# 01_MAIN.net
KiCad netlist of a schematic drawn in Altium Designer
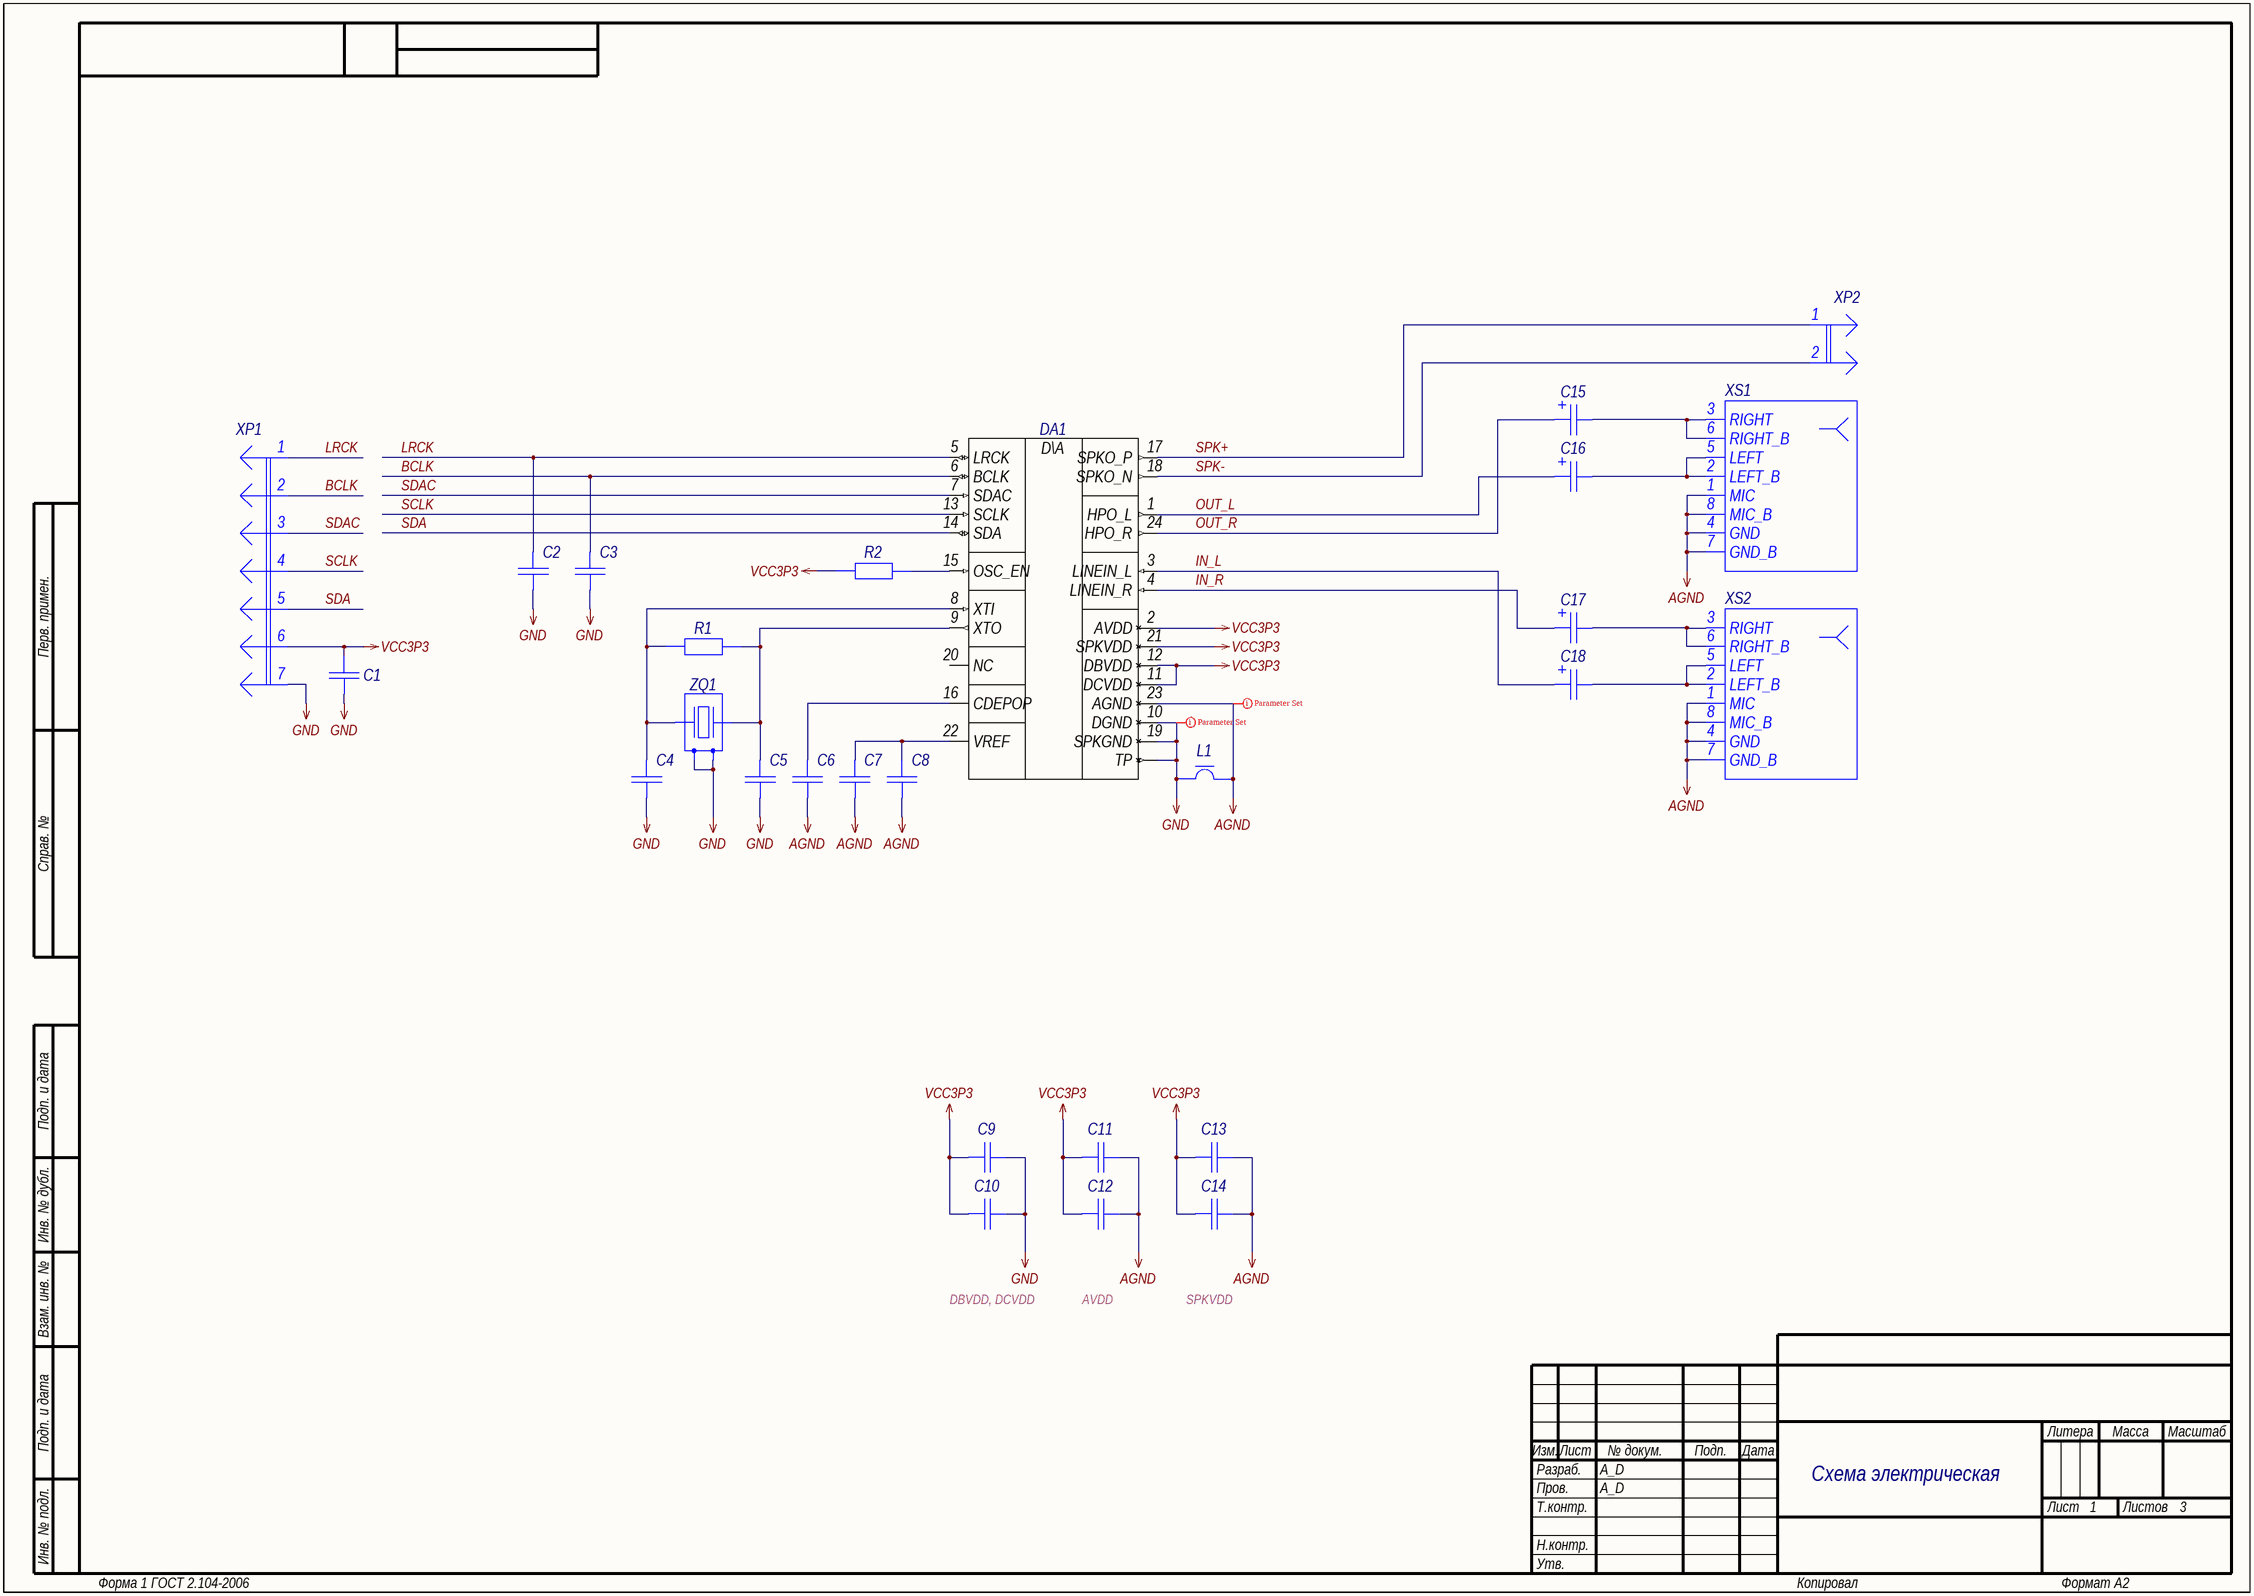
[diagram p0: 01_MAIN.SchDoc]

(export (version "E")
  (design (tool "Eeschema 10.0.6"))
  (components
    (comp (ref "C1")
      (value "Capacitor")
      (footprint "C0805_L")
      (fields
        (field (name "PART NUMBER") "GRM21BR60J226ME39L")
        (field (name "VOLTAGE") "6.3V")
        (field (name "TOLERANCE") "±20%")
        (field (name "PUBLISHER") "Andrew Danich")
      )
      (libsource (lib "ADLib") (part "Capacitor"))
    )
    (comp (ref "C2")
      (value "Capacitor")
      (footprint "C0603_L")
      (fields
        (field (name "PART NUMBER") "GRM1885C1H220JA01D")
        (field (name "VOLTAGE") "50V")
        (field (name "TOLERANCE") "±5%")
        (field (name "PUBLISHER") "Andrew Danich")
      )
      (libsource (lib "ADLib") (part "Capacitor"))
    )
    (comp (ref "C3")
      (value "Capacitor")
      (footprint "C0603_L")
      (fields
        (field (name "PART NUMBER") "GRM1885C1H220JA01D")
        (field (name "VOLTAGE") "50V")
        (field (name "TOLERANCE") "±5%")
        (field (name "PUBLISHER") "Andrew Danich")
      )
      (libsource (lib "ADLib") (part "Capacitor"))
    )
    (comp (ref "C4")
      (value "Capacitor")
      (footprint "C0603_L")
      (fields
        (field (name "PART NUMBER") "GCM1885C2A120JA16D")
        (field (name "VOLTAGE") "100V")
        (field (name "TOLERANCE") "±5%")
        (field (name "PUBLISHER") "Andrew Danich")
      )
      (libsource (lib "ADLib") (part "Capacitor"))
    )
    (comp (ref "C5")
      (value "Capacitor")
      (footprint "C0603_L")
      (fields
        (field (name "PART NUMBER") "GCM1885C2A120JA16D")
        (field (name "VOLTAGE") "100V")
        (field (name "TOLERANCE") "±5%")
        (field (name "PUBLISHER") "Andrew Danich")
      )
      (libsource (lib "ADLib") (part "Capacitor"))
    )
    (comp (ref "C6")
      (value "Capacitor")
      (footprint "C0603_L")
      (fields
        (field (name "PART NUMBER") "GCM188R71E105KA64D")
        (field (name "VOLTAGE") "25V")
        (field (name "TOLERANCE") "±10%")
        (field (name "PUBLISHER") "Andrew Danich")
      )
      (libsource (lib "ADLib") (part "Capacitor"))
    )
    (comp (ref "C7")
      (value "Capacitor")
      (footprint "C0603_L")
      (fields
        (field (name "PART NUMBER") "GRM188R72A104KA35D")
        (field (name "VOLTAGE") "100V")
        (field (name "TOLERANCE") "±10%")
        (field (name "PUBLISHER") "Andrew Danich")
      )
      (libsource (lib "ADLib") (part "Capacitor"))
    )
    (comp (ref "C8")
      (value "Capacitor")
      (footprint "C0603_L")
      (fields
        (field (name "PART NUMBER") "GRT188C81E475KE13D")
        (field (name "VOLTAGE") "25V")
        (field (name "TOLERANCE") "±20%")
        (field (name "PUBLISHER") "Andrew Danich")
      )
      (libsource (lib "ADLib") (part "Capacitor"))
    )
    (comp (ref "C9")
      (value "Capacitor")
      (footprint "C0603_L")
      (fields
        (field (name "PART NUMBER") "GCM188R71E105KA64D")
        (field (name "VOLTAGE") "25V")
        (field (name "TOLERANCE") "±10%")
        (field (name "PUBLISHER") "Andrew Danich")
      )
      (libsource (lib "ADLib") (part "Capacitor"))
    )
    (comp (ref "C10")
      (value "Capacitor")
      (footprint "C0603_L")
      (fields
        (field (name "PART NUMBER") "GRM1885C2A102JA01D")
        (field (name "VOLTAGE") "100V")
        (field (name "TOLERANCE") "±5%")
        (field (name "PUBLISHER") "Andrew Danich")
      )
      (libsource (lib "ADLib") (part "Capacitor"))
    )
    (comp (ref "C11")
      (value "Capacitor")
      (footprint "C0603_L")
      (fields
        (field (name "PART NUMBER") "GCM188R71E105KA64D")
        (field (name "VOLTAGE") "25V")
        (field (name "TOLERANCE") "±10%")
        (field (name "PUBLISHER") "Andrew Danich")
      )
      (libsource (lib "ADLib") (part "Capacitor"))
    )
    (comp (ref "C12")
      (value "Capacitor")
      (footprint "C0603_L")
      (fields
        (field (name "PART NUMBER") "GRM1885C2A102JA01D")
        (field (name "VOLTAGE") "100V")
        (field (name "TOLERANCE") "±5%")
        (field (name "PUBLISHER") "Andrew Danich")
      )
      (libsource (lib "ADLib") (part "Capacitor"))
    )
    (comp (ref "C13")
      (value "Capacitor")
      (footprint "C0603_L")
      (fields
        (field (name "PART NUMBER") "GRM188C80J106MA73D")
        (field (name "VOLTAGE") "6.3V")
        (field (name "TOLERANCE") "±20%")
        (field (name "PUBLISHER") "Andrew Danich")
      )
      (libsource (lib "ADLib") (part "Capacitor"))
    )
    (comp (ref "C14")
      (value "Capacitor")
      (footprint "C0603_L")
      (fields
        (field (name "PART NUMBER") "GRM1885C2A102JA01D")
        (field (name "VOLTAGE") "100V")
        (field (name "TOLERANCE") "±5%")
        (field (name "PUBLISHER") "Andrew Danich")
      )
      (libsource (lib "ADLib") (part "Capacitor"))
    )
    (comp (ref "C15")
      (value "Capacitor-T")
      (footprint "C3528-p")
      (fields
        (field (name "PART NUMBER") "T520B107M006ATE040")
        (field (name "VOLTAGE") "6.3V")
        (field (name "TOLERANCE") "±20%")
        (field (name "PUBLISHER") "Andrew Danich")
      )
      (libsource (lib "ADLib") (part "Capacitor-T"))
    )
    (comp (ref "C16")
      (value "Capacitor-T")
      (footprint "C3528-p")
      (fields
        (field (name "PART NUMBER") "T520B107M006ATE040")
        (field (name "VOLTAGE") "6.3V")
        (field (name "TOLERANCE") "±20%")
        (field (name "PUBLISHER") "Andrew Danich")
      )
      (libsource (lib "ADLib") (part "Capacitor-T"))
    )
    (comp (ref "C17")
      (value "Capacitor-T")
      (footprint "C3216-p")
      (fields
        (field (name "PART NUMBER") "293D105X9016A2TE3")
        (field (name "VOLTAGE") "16V")
        (field (name "TOLERANCE") "±10%")
        (field (name "PUBLISHER") "Andrew Danich")
      )
      (libsource (lib "ADLib") (part "Capacitor-T"))
    )
    (comp (ref "C18")
      (value "Capacitor-T")
      (footprint "C3216-p")
      (fields
        (field (name "PART NUMBER") "293D105X9016A2TE3")
        (field (name "VOLTAGE") "16V")
        (field (name "TOLERANCE") "±10%")
        (field (name "PUBLISHER") "Andrew Danich")
      )
      (libsource (lib "ADLib") (part "Capacitor-T"))
    )
    (comp (ref "DA1")
      (value "ALC5628")
      (footprint "QFN-24_050P400X400X090_N")
      (fields
        (field (name "PART NUMBER") "ALC5628-GR")
        (field (name "MANUFACTURER") "Realtek")
        (field (name "PUBLISHER") "Andrew Danich")
      )
      (libsource (lib "ADLib") (part "ALC5628"))
    )
    (comp (ref "L1")
      (value "FerriteBead")
      (footprint "L0603_L")
      (fields
        (field (name "PART NUMBER") "BLM18PG121SN1")
        (field (name "MANUFACTURER") "Murata")
        (field (name "PUBLISHER") "Andrew Danich")
      )
      (libsource (lib "ADLib") (part "FerriteBead"))
    )
    (comp (ref "R1")
      (value "Resistor")
      (footprint "R0603_L")
      (fields
        (field (name "PART NUMBER") "RC0603JR-071ML")
        (field (name "TOLERANCE") "±5%")
        (field (name "MANUFACTURER") "Yageo")
        (field (name "PUBLISHER") "Andrew Danich")
      )
      (libsource (lib "ADLib") (part "Resistor"))
    )
    (comp (ref "R2")
      (value "Resistor")
      (footprint "R0603_L")
      (fields
        (field (name "PART NUMBER") "RC0603JR-070R")
        (field (name "TOLERANCE") "±5%")
        (field (name "MANUFACTURER") "Yageo")
        (field (name "PUBLISHER") "Andrew Danich")
      )
      (libsource (lib "ADLib") (part "Resistor"))
    )
    (comp (ref "XP1")
      (value "Text")
      (footprint "PLS-7")
      (fields (field (name "PART NUMBER") "PLS-7") (field (name "PUBLISHER") "Andrew Danich"))
      (libsource (lib "ADLib") (part "Con-7-M"))
    )
    (comp (ref "XP2")
      (value "SPK")
      (footprint "PLS-2")
      (fields (field (name "PART NUMBER") "PLS-2") (field (name "PUBLISHER") "Andrew Danich"))
      (libsource (lib "ADLib") (part "Con-2-M"))
    )
    (comp (ref "XS1")
      (value "OUT")
      (footprint "PJ30930-Series")
      (fields
        (field (name "PART NUMBER") "PJ30930-Q-LC0AG00TR-7260")
        (field (name "MANUFACTURER") "Dongnan Electronics")
        (field (name "PUBLISHER") "Andrew Danich")
      )
      (libsource (lib "ADLib") (part "PJ30930-Q-LCxx00x-7260"))
    )
    (comp (ref "XS2")
      (value "IN")
      (footprint "PJ30930-Series")
      (fields
        (field (name "PART NUMBER") "PJ30930-Q-LC0AG00TR-7260")
        (field (name "MANUFACTURER") "Dongnan Electronics")
        (field (name "PUBLISHER") "Andrew Danich")
      )
      (libsource (lib "ADLib") (part "PJ30930-Q-LCxx00x-7260"))
    )
    (comp (ref "ZQ1")
      (value "Crystal-1_3p_S")
      (footprint "SMD 3.2x2.5mm")
      (fields
        (field (name "PART NUMBER") "MCSJK-7U-24.576-12-30-60-B-30")
        (field (name "MANUFACTURER") "Multicomp")
        (field (name "PUBLISHER") "Andrew Danich")
      )
      (libsource (lib "ADLib") (part "Crystal-1_3p_S"))
    )
  )
  (nets
    (net (code "1") (name "/BCLK") (class "Default")
      (node (ref "C3") (pin "2") (pinfunction "2_2") (pintype "passive"))
      (node (ref "DA1") (pin "6") (pinfunction "BCLK_6") (pintype "bidirectional"))
      (node (ref "XP1") (pin "2") (pintype "passive"))
    )
    (net (code "2") (name "/IN_L") (class "Default")
      (node (ref "C18") (pin "1") (pinfunction "1_1") (pintype "passive"))
      (node (ref "DA1") (pin "3") (pinfunction "LINEIN_L_3") (pintype "input"))
    )
    (net (code "3") (name "/IN_R") (class "Default")
      (node (ref "C17") (pin "1") (pinfunction "1_1") (pintype "passive"))
      (node (ref "DA1") (pin "4") (pinfunction "LINEIN_R_4") (pintype "input"))
    )
    (net (code "4") (name "/LRCK") (class "Default")
      (node (ref "C2") (pin "2") (pinfunction "2_2") (pintype "passive"))
      (node (ref "DA1") (pin "5") (pinfunction "LRCK_5") (pintype "bidirectional"))
      (node (ref "XP1") (pin "1") (pintype "passive"))
    )
    (net (code "5") (name "/OUT_L") (class "Default")
      (node (ref "C16") (pin "1") (pinfunction "1_1") (pintype "passive"))
      (node (ref "DA1") (pin "1") (pinfunction "HPO_L_1") (pintype "output"))
    )
    (net (code "6") (name "/OUT_R") (class "Default")
      (node (ref "C15") (pin "1") (pinfunction "1_1") (pintype "passive"))
      (node (ref "DA1") (pin "24") (pinfunction "HPO_R_24") (pintype "output"))
    )
    (net (code "7") (name "/SCLK") (class "Default")
      (node (ref "DA1") (pin "13") (pinfunction "SCLK_13") (pintype "input"))
      (node (ref "XP1") (pin "4") (pintype "passive"))
    )
    (net (code "8") (name "/SDA") (class "Default")
      (node (ref "DA1") (pin "14") (pinfunction "SDA_14") (pintype "bidirectional"))
      (node (ref "XP1") (pin "5") (pintype "passive"))
    )
    (net (code "9") (name "/SDAC") (class "Default")
      (node (ref "DA1") (pin "7") (pinfunction "SDAC_7") (pintype "input"))
      (node (ref "XP1") (pin "3") (pintype "passive"))
    )
    (net (code "10") (name "/SPK+") (class "Default")
      (node (ref "DA1") (pin "17") (pinfunction "SPKO_P_17") (pintype "output"))
      (node (ref "XP2") (pin "1") (pintype "passive"))
    )
    (net (code "11") (name "/SPK-") (class "Default")
      (node (ref "DA1") (pin "18") (pinfunction "SPKO_N_18") (pintype "output"))
      (node (ref "XP2") (pin "2") (pintype "passive"))
    )
    (net (code "12") (name "AGND") (class "Default")
      (node (ref "C11") (pin "2") (pinfunction "2_2") (pintype "passive"))
      (node (ref "C12") (pin "2") (pinfunction "2_2") (pintype "passive"))
      (node (ref "C13") (pin "2") (pinfunction "2_2") (pintype "passive"))
      (node (ref "C14") (pin "2") (pinfunction "2_2") (pintype "passive"))
      (node (ref "C6") (pin "1") (pinfunction "1_1") (pintype "passive"))
      (node (ref "C7") (pin "1") (pinfunction "1_1") (pintype "passive"))
      (node (ref "C8") (pin "1") (pinfunction "1_1") (pintype "passive"))
      (node (ref "DA1") (pin "23") (pinfunction "AGND_23") (pintype "power_in"))
      (node (ref "L1") (pin "2") (pinfunction "2_2") (pintype "passive"))
      (node (ref "XS1") (pin "1") (pinfunction "MIC_1") (pintype "passive"))
      (node (ref "XS1") (pin "4") (pinfunction "GND_4") (pintype "passive"))
      (node (ref "XS1") (pin "7") (pinfunction "GND_B_7") (pintype "passive"))
      (node (ref "XS1") (pin "8") (pinfunction "MIC_B_8") (pintype "passive"))
      (node (ref "XS2") (pin "1") (pinfunction "MIC_1") (pintype "passive"))
      (node (ref "XS2") (pin "4") (pinfunction "GND_4") (pintype "passive"))
      (node (ref "XS2") (pin "7") (pinfunction "GND_B_7") (pintype "passive"))
      (node (ref "XS2") (pin "8") (pinfunction "MIC_B_8") (pintype "passive"))
    )
    (net (code "13") (name "GND") (class "Default")
      (node (ref "C1") (pin "1") (pinfunction "1_1") (pintype "passive"))
      (node (ref "C10") (pin "2") (pinfunction "2_2") (pintype "passive"))
      (node (ref "C2") (pin "1") (pinfunction "1_1") (pintype "passive"))
      (node (ref "C3") (pin "1") (pinfunction "1_1") (pintype "passive"))
      (node (ref "C4") (pin "1") (pinfunction "1_1") (pintype "passive"))
      (node (ref "C5") (pin "1") (pinfunction "1_1") (pintype "passive"))
      (node (ref "C9") (pin "2") (pinfunction "2_2") (pintype "passive"))
      (node (ref "DA1") (pin "10") (pinfunction "DGND_10") (pintype "power_in"))
      (node (ref "DA1") (pin "19") (pinfunction "SPKGND_19") (pintype "power_in"))
      (node (ref "DA1") (pin "TP") (pinfunction "TP_TP") (pintype "output"))
      (node (ref "L1") (pin "1") (pinfunction "1_1") (pintype "passive"))
      (node (ref "XP1") (pin "7") (pintype "passive"))
      (node (ref "ZQ1") (pin "2") (pinfunction "2_2") (pintype "passive"))
      (node (ref "ZQ1") (pin "4") (pinfunction "4_4") (pintype "passive"))
    )
    (net (code "14") (name "Net-(DA1-CDEPOP)") (class "Default")
      (node (ref "C6") (pin "2") (pinfunction "2_2") (pintype "passive"))
      (node (ref "DA1") (pin "16") (pinfunction "CDEPOP_16") (pintype "passive"))
    )
    (net (code "15") (name "Net-(DA1-OSC_EN)") (class "Default")
      (node (ref "DA1") (pin "15") (pinfunction "OSC_EN_15") (pintype "input"))
      (node (ref "R2") (pin "2") (pinfunction "2_2") (pintype "passive"))
    )
    (net (code "16") (name "Net-(DA1-VREF)") (class "Default")
      (node (ref "C7") (pin "2") (pinfunction "2_2") (pintype "passive"))
      (node (ref "C8") (pin "2") (pinfunction "2_2") (pintype "passive"))
      (node (ref "DA1") (pin "22") (pinfunction "VREF_22") (pintype "passive"))
    )
    (net (code "17") (name "Net-(DA1-XTI)") (class "Default")
      (node (ref "C4") (pin "2") (pinfunction "2_2") (pintype "passive"))
      (node (ref "DA1") (pin "8") (pinfunction "XTI_8") (pintype "input"))
      (node (ref "R1") (pin "1") (pinfunction "1_1") (pintype "passive"))
      (node (ref "ZQ1") (pin "1") (pinfunction "1_1") (pintype "passive"))
    )
    (net (code "18") (name "Net-(DA1-XTO)") (class "Default")
      (node (ref "C5") (pin "2") (pinfunction "2_2") (pintype "passive"))
      (node (ref "DA1") (pin "9") (pinfunction "XTO_9") (pintype "output"))
      (node (ref "R1") (pin "2") (pinfunction "2_2") (pintype "passive"))
      (node (ref "ZQ1") (pin "3") (pinfunction "3_3") (pintype "passive"))
    )
    (net (code "19") (name "Net-(XS1-LEFT)") (class "Default")
      (node (ref "C16") (pin "2") (pinfunction "2_2") (pintype "passive"))
      (node (ref "XS1") (pin "2") (pinfunction "LEFT_B_2") (pintype "passive"))
      (node (ref "XS1") (pin "5") (pinfunction "LEFT_5") (pintype "passive"))
    )
    (net (code "20") (name "Net-(XS1-RIGHT)") (class "Default")
      (node (ref "C15") (pin "2") (pinfunction "2_2") (pintype "passive"))
      (node (ref "XS1") (pin "3") (pinfunction "RIGHT_3") (pintype "passive"))
      (node (ref "XS1") (pin "6") (pinfunction "RIGHT_B_6") (pintype "passive"))
    )
    (net (code "21") (name "Net-(XS2-LEFT)") (class "Default")
      (node (ref "C18") (pin "2") (pinfunction "2_2") (pintype "passive"))
      (node (ref "XS2") (pin "2") (pinfunction "LEFT_B_2") (pintype "passive"))
      (node (ref "XS2") (pin "5") (pinfunction "LEFT_5") (pintype "passive"))
    )
    (net (code "22") (name "Net-(XS2-RIGHT)") (class "Default")
      (node (ref "C17") (pin "2") (pinfunction "2_2") (pintype "passive"))
      (node (ref "XS2") (pin "3") (pinfunction "RIGHT_3") (pintype "passive"))
      (node (ref "XS2") (pin "6") (pinfunction "RIGHT_B_6") (pintype "passive"))
    )
    (net (code "23") (name "VCC3P3") (class "Default")
      (node (ref "C1") (pin "2") (pinfunction "2_2") (pintype "passive"))
      (node (ref "C10") (pin "1") (pinfunction "1_1") (pintype "passive"))
      (node (ref "C11") (pin "1") (pinfunction "1_1") (pintype "passive"))
      (node (ref "C12") (pin "1") (pinfunction "1_1") (pintype "passive"))
      (node (ref "C13") (pin "1") (pinfunction "1_1") (pintype "passive"))
      (node (ref "C14") (pin "1") (pinfunction "1_1") (pintype "passive"))
      (node (ref "C9") (pin "1") (pinfunction "1_1") (pintype "passive"))
      (node (ref "DA1") (pin "11") (pinfunction "DCVDD_11") (pintype "power_in"))
      (node (ref "DA1") (pin "12") (pinfunction "DBVDD_12") (pintype "power_in"))
      (node (ref "DA1") (pin "2") (pinfunction "AVDD_2") (pintype "power_in"))
      (node (ref "DA1") (pin "21") (pinfunction "SPKVDD_21") (pintype "power_in"))
      (node (ref "R2") (pin "1") (pinfunction "1_1") (pintype "passive"))
      (node (ref "XP1") (pin "6") (pintype "passive"))
    )
    (net (code "24") (name "unconnected-(DA1-NC-Pad20)") (class "Default")
      (node (ref "DA1") (pin "20") (pinfunction "NC_20") (pintype "passive"))
    )
  )
)
